# EndEffector-_Connectors.net
KiCad netlist of a schematic drawn in Altium Designer
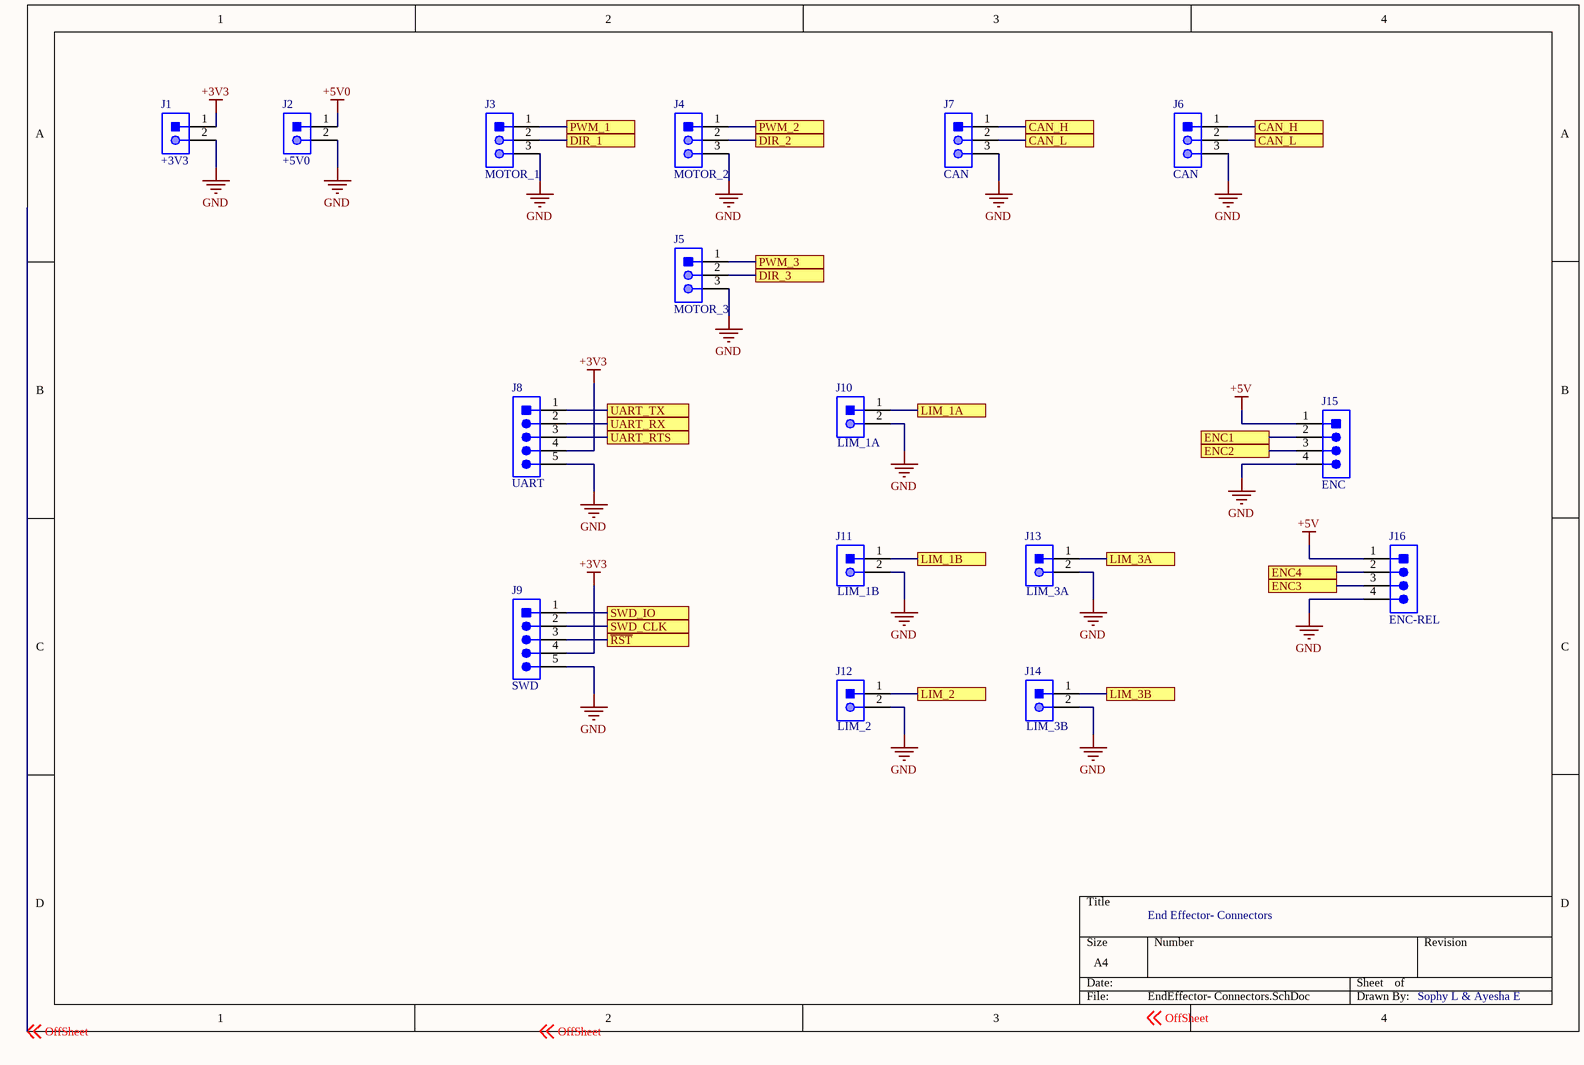
[diagram p0: EndEffector- Connectors.SchDoc]

(export (version "E")
  (design (tool "Eeschema 10.0.6"))
  (components
    (comp (ref "J1")
      (value "+3V3")
      (description "CONN HEADER PH SIDE 2POS 2MM SMD")
      (fields (field (name "MANUFACTURER") "JST") (field (name "PART NUMBER") "S2B-PH-SM4-TB"))
      (libsource (lib "UWRT_Schematic_Library_2019") (part "CON_2M_PH_SIDE_SMT"))
    )
    (comp (ref "J2")
      (value "+5V0")
      (description "CONN HEADER PH SIDE 2POS 2MM SMD")
      (fields (field (name "MANUFACTURER") "JST") (field (name "PART NUMBER") "S2B-PH-SM4-TB"))
      (libsource (lib "UWRT_Schematic_Library_2019") (part "CON_2M_PH_SIDE_SMT"))
    )
    (comp (ref "J3")
      (value "MOTOR_1")
      (description "CONN HEADER PH SIDE 3POS 2MM SMD")
      (fields (field (name "MANUFACTURER") "JST") (field (name "PART NUMBER") "B3B-PH-SM4-TB"))
      (libsource (lib "UWRT_Schematic_Library_2019") (part "CON_3M_PH_SIDE_SMT"))
    )
    (comp (ref "J4")
      (value "MOTOR_2")
      (description "CONN HEADER PH SIDE 3POS 2MM SMD")
      (fields (field (name "MANUFACTURER") "JST") (field (name "PART NUMBER") "B3B-PH-SM4-TB"))
      (libsource (lib "UWRT_Schematic_Library_2019") (part "CON_3M_PH_SIDE_SMT"))
    )
    (comp (ref "J5")
      (value "MOTOR_3")
      (description "CONN HEADER PH SIDE 3POS 2MM SMD")
      (fields (field (name "MANUFACTURER") "JST") (field (name "PART NUMBER") "B3B-PH-SM4-TB"))
      (libsource (lib "UWRT_Schematic_Library_2019") (part "CON_3M_PH_SIDE_SMT"))
    )
    (comp (ref "J6")
      (value "CAN")
      (description "CONN HEADER PH SIDE 3POS 2MM SMD")
      (fields (field (name "MANUFACTURER") "JST") (field (name "PART NUMBER") "B3B-PH-SM4-TB"))
      (libsource (lib "UWRT_Schematic_Library_2019") (part "CON_3M_PH_SIDE_SMT"))
    )
    (comp (ref "J7")
      (value "CAN")
      (description "CONN HEADER PH SIDE 3POS 2MM SMD")
      (fields (field (name "MANUFACTURER") "JST") (field (name "PART NUMBER") "B3B-PH-SM4-TB"))
      (libsource (lib "UWRT_Schematic_Library_2019") (part "CON_3M_PH_SIDE_SMT"))
    )
    (comp (ref "J8")
      (value "UART")
      (description "CONN HEADER PH SIDE 5POS 2MM")
      (fields (field (name "MANUFACTURER") "JST") (field (name "PART NUMBER") "S5B-PH-K-S"))
      (libsource (lib "UWRT_Schematic_Library_2019") (part "CON_5M_PH_SIDE_TH"))
    )
    (comp (ref "J9")
      (value "SWD")
      (description "CONN HEADER PH SIDE 5POS 2MM")
      (fields (field (name "MANUFACTURER") "JST") (field (name "PART NUMBER") "S5B-PH-K-S"))
      (libsource (lib "UWRT_Schematic_Library_2019") (part "CON_5M_PH_SIDE_TH"))
    )
    (comp (ref "J10")
      (value "LIM_1A")
      (description "CONN HEADER PH SIDE 2POS 2MM SMD")
      (fields (field (name "MANUFACTURER") "JST") (field (name "PART NUMBER") "S2B-PH-SM4-TB"))
      (libsource (lib "UWRT_Schematic_Library_2019") (part "CON_2M_PH_SIDE_SMT"))
    )
    (comp (ref "J11")
      (value "LIM_1B")
      (description "CONN HEADER PH SIDE 2POS 2MM SMD")
      (fields (field (name "MANUFACTURER") "JST") (field (name "PART NUMBER") "S2B-PH-SM4-TB"))
      (libsource (lib "UWRT_Schematic_Library_2019") (part "CON_2M_PH_SIDE_SMT"))
    )
    (comp (ref "J12")
      (value "LIM_2")
      (description "CONN HEADER PH SIDE 2POS 2MM SMD")
      (fields (field (name "MANUFACTURER") "JST") (field (name "PART NUMBER") "S2B-PH-SM4-TB"))
      (libsource (lib "UWRT_Schematic_Library_2019") (part "CON_2M_PH_SIDE_SMT"))
    )
    (comp (ref "J13")
      (value "LIM_3A")
      (description "CONN HEADER PH SIDE 2POS 2MM SMD")
      (fields (field (name "MANUFACTURER") "JST") (field (name "PART NUMBER") "S2B-PH-SM4-TB"))
      (libsource (lib "UWRT_Schematic_Library_2019") (part "CON_2M_PH_SIDE_SMT"))
    )
    (comp (ref "J14")
      (value "LIM_3B")
      (description "CONN HEADER PH SIDE 2POS 2MM SMD")
      (fields (field (name "MANUFACTURER") "JST") (field (name "PART NUMBER") "S2B-PH-SM4-TB"))
      (libsource (lib "UWRT_Schematic_Library_2019") (part "CON_2M_PH_SIDE_SMT"))
    )
    (comp (ref "J15")
      (value "ENC")
      (description "CONN HEADER PH SIDE 4POS 2MM SMD")
      (fields (field (name "MANUFACTURER") "JST") (field (name "PART NUMBER") "B4B-PH-SM4-TB"))
      (libsource (lib "UWRT_Schematic_Library_2019") (part "CON_4M_PH_SIDE_SMT"))
    )
    (comp (ref "J16")
      (value "ENC-REL")
      (description "CONN HEADER PH SIDE 4POS 2MM SMD")
      (fields (field (name "MANUFACTURER") "JST") (field (name "PART NUMBER") "B4B-PH-SM4-TB"))
      (libsource (lib "UWRT_Schematic_Library_2019") (part "CON_4M_PH_SIDE_SMT"))
    )
  )
  (nets
    (net (code "1") (name "+3V3") (class "Default")
      (node (ref "J1") (pin "1") (pinfunction "1_1") (pintype "passive"))
      (node (ref "J8") (pin "4") (pinfunction "4_4") (pintype "passive"))
      (node (ref "J9") (pin "4") (pinfunction "4_4") (pintype "passive"))
    )
    (net (code "2") (name "+5V") (class "Default")
      (node (ref "J15") (pin "1") (pinfunction "1_1") (pintype "passive"))
      (node (ref "J16") (pin "1") (pinfunction "1_1") (pintype "passive"))
    )
    (net (code "3") (name "+5V0") (class "Default")
      (node (ref "J2") (pin "1") (pinfunction "1_1") (pintype "passive"))
    )
    (net (code "4") (name "/CAN_H") (class "Default")
      (node (ref "J6") (pin "1") (pinfunction "1_1") (pintype "passive"))
      (node (ref "J7") (pin "1") (pinfunction "1_1") (pintype "passive"))
    )
    (net (code "5") (name "/CAN_L") (class "Default")
      (node (ref "J6") (pin "2") (pinfunction "2_2") (pintype "passive"))
      (node (ref "J7") (pin "2") (pinfunction "2_2") (pintype "passive"))
    )
    (net (code "6") (name "/DIR_1") (class "Default")
      (node (ref "J3") (pin "2") (pinfunction "2_2") (pintype "passive"))
    )
    (net (code "7") (name "/DIR_2") (class "Default")
      (node (ref "J4") (pin "2") (pinfunction "2_2") (pintype "passive"))
    )
    (net (code "8") (name "/DIR_3") (class "Default")
      (node (ref "J5") (pin "2") (pinfunction "2_2") (pintype "passive"))
    )
    (net (code "9") (name "/ENC1") (class "Default")
      (node (ref "J15") (pin "2") (pinfunction "2_2") (pintype "passive"))
    )
    (net (code "10") (name "/ENC2") (class "Default")
      (node (ref "J15") (pin "3") (pinfunction "3_3") (pintype "passive"))
    )
    (net (code "11") (name "/ENC3") (class "Default")
      (node (ref "J16") (pin "3") (pinfunction "3_3") (pintype "passive"))
    )
    (net (code "12") (name "/ENC4") (class "Default")
      (node (ref "J16") (pin "2") (pinfunction "2_2") (pintype "passive"))
    )
    (net (code "13") (name "/LIM_1A") (class "Default")
      (node (ref "J10") (pin "1") (pinfunction "1_1") (pintype "passive"))
    )
    (net (code "14") (name "/LIM_1B") (class "Default")
      (node (ref "J11") (pin "1") (pinfunction "1_1") (pintype "passive"))
    )
    (net (code "15") (name "/LIM_2") (class "Default")
      (node (ref "J12") (pin "1") (pinfunction "1_1") (pintype "passive"))
    )
    (net (code "16") (name "/LIM_3A") (class "Default")
      (node (ref "J13") (pin "1") (pinfunction "1_1") (pintype "passive"))
    )
    (net (code "17") (name "/LIM_3B") (class "Default")
      (node (ref "J14") (pin "1") (pinfunction "1_1") (pintype "passive"))
    )
    (net (code "18") (name "/PWM_1") (class "Default")
      (node (ref "J3") (pin "1") (pinfunction "1_1") (pintype "passive"))
    )
    (net (code "19") (name "/PWM_2") (class "Default")
      (node (ref "J4") (pin "1") (pinfunction "1_1") (pintype "passive"))
    )
    (net (code "20") (name "/PWM_3") (class "Default")
      (node (ref "J5") (pin "1") (pinfunction "1_1") (pintype "passive"))
    )
    (net (code "21") (name "/SWD_CLK") (class "Default")
      (node (ref "J9") (pin "2") (pinfunction "2_2") (pintype "passive"))
    )
    (net (code "22") (name "/SWD_IO") (class "Default")
      (node (ref "J9") (pin "1") (pinfunction "1_1") (pintype "passive"))
    )
    (net (code "23") (name "/UART_RTS") (class "Default")
      (node (ref "J8") (pin "3") (pinfunction "3_3") (pintype "passive"))
    )
    (net (code "24") (name "/UART_RX") (class "Default")
      (node (ref "J8") (pin "2") (pinfunction "2_2") (pintype "passive"))
    )
    (net (code "25") (name "/UART_TX") (class "Default")
      (node (ref "J8") (pin "1") (pinfunction "1_1") (pintype "passive"))
    )
    (net (code "26") (name "/~{RST}") (class "Default")
      (node (ref "J9") (pin "3") (pinfunction "3_3") (pintype "passive"))
    )
    (net (code "27") (name "GND") (class "Default")
      (node (ref "J1") (pin "2") (pinfunction "2_2") (pintype "passive"))
      (node (ref "J10") (pin "2") (pinfunction "2_2") (pintype "passive"))
      (node (ref "J11") (pin "2") (pinfunction "2_2") (pintype "passive"))
      (node (ref "J12") (pin "2") (pinfunction "2_2") (pintype "passive"))
      (node (ref "J13") (pin "2") (pinfunction "2_2") (pintype "passive"))
      (node (ref "J14") (pin "2") (pinfunction "2_2") (pintype "passive"))
      (node (ref "J15") (pin "4") (pinfunction "4_4") (pintype "passive"))
      (node (ref "J16") (pin "4") (pinfunction "4_4") (pintype "passive"))
      (node (ref "J2") (pin "2") (pinfunction "2_2") (pintype "passive"))
      (node (ref "J3") (pin "3") (pinfunction "3_3") (pintype "passive"))
      (node (ref "J4") (pin "3") (pinfunction "3_3") (pintype "passive"))
      (node (ref "J5") (pin "3") (pinfunction "3_3") (pintype "passive"))
      (node (ref "J6") (pin "3") (pinfunction "3_3") (pintype "passive"))
      (node (ref "J7") (pin "3") (pinfunction "3_3") (pintype "passive"))
      (node (ref "J8") (pin "5") (pinfunction "5_5") (pintype "passive"))
      (node (ref "J9") (pin "5") (pinfunction "5_5") (pintype "passive"))
    )
  )
)
